# zx81c.net
KiCad netlist of a schematic drawn in EAGLE
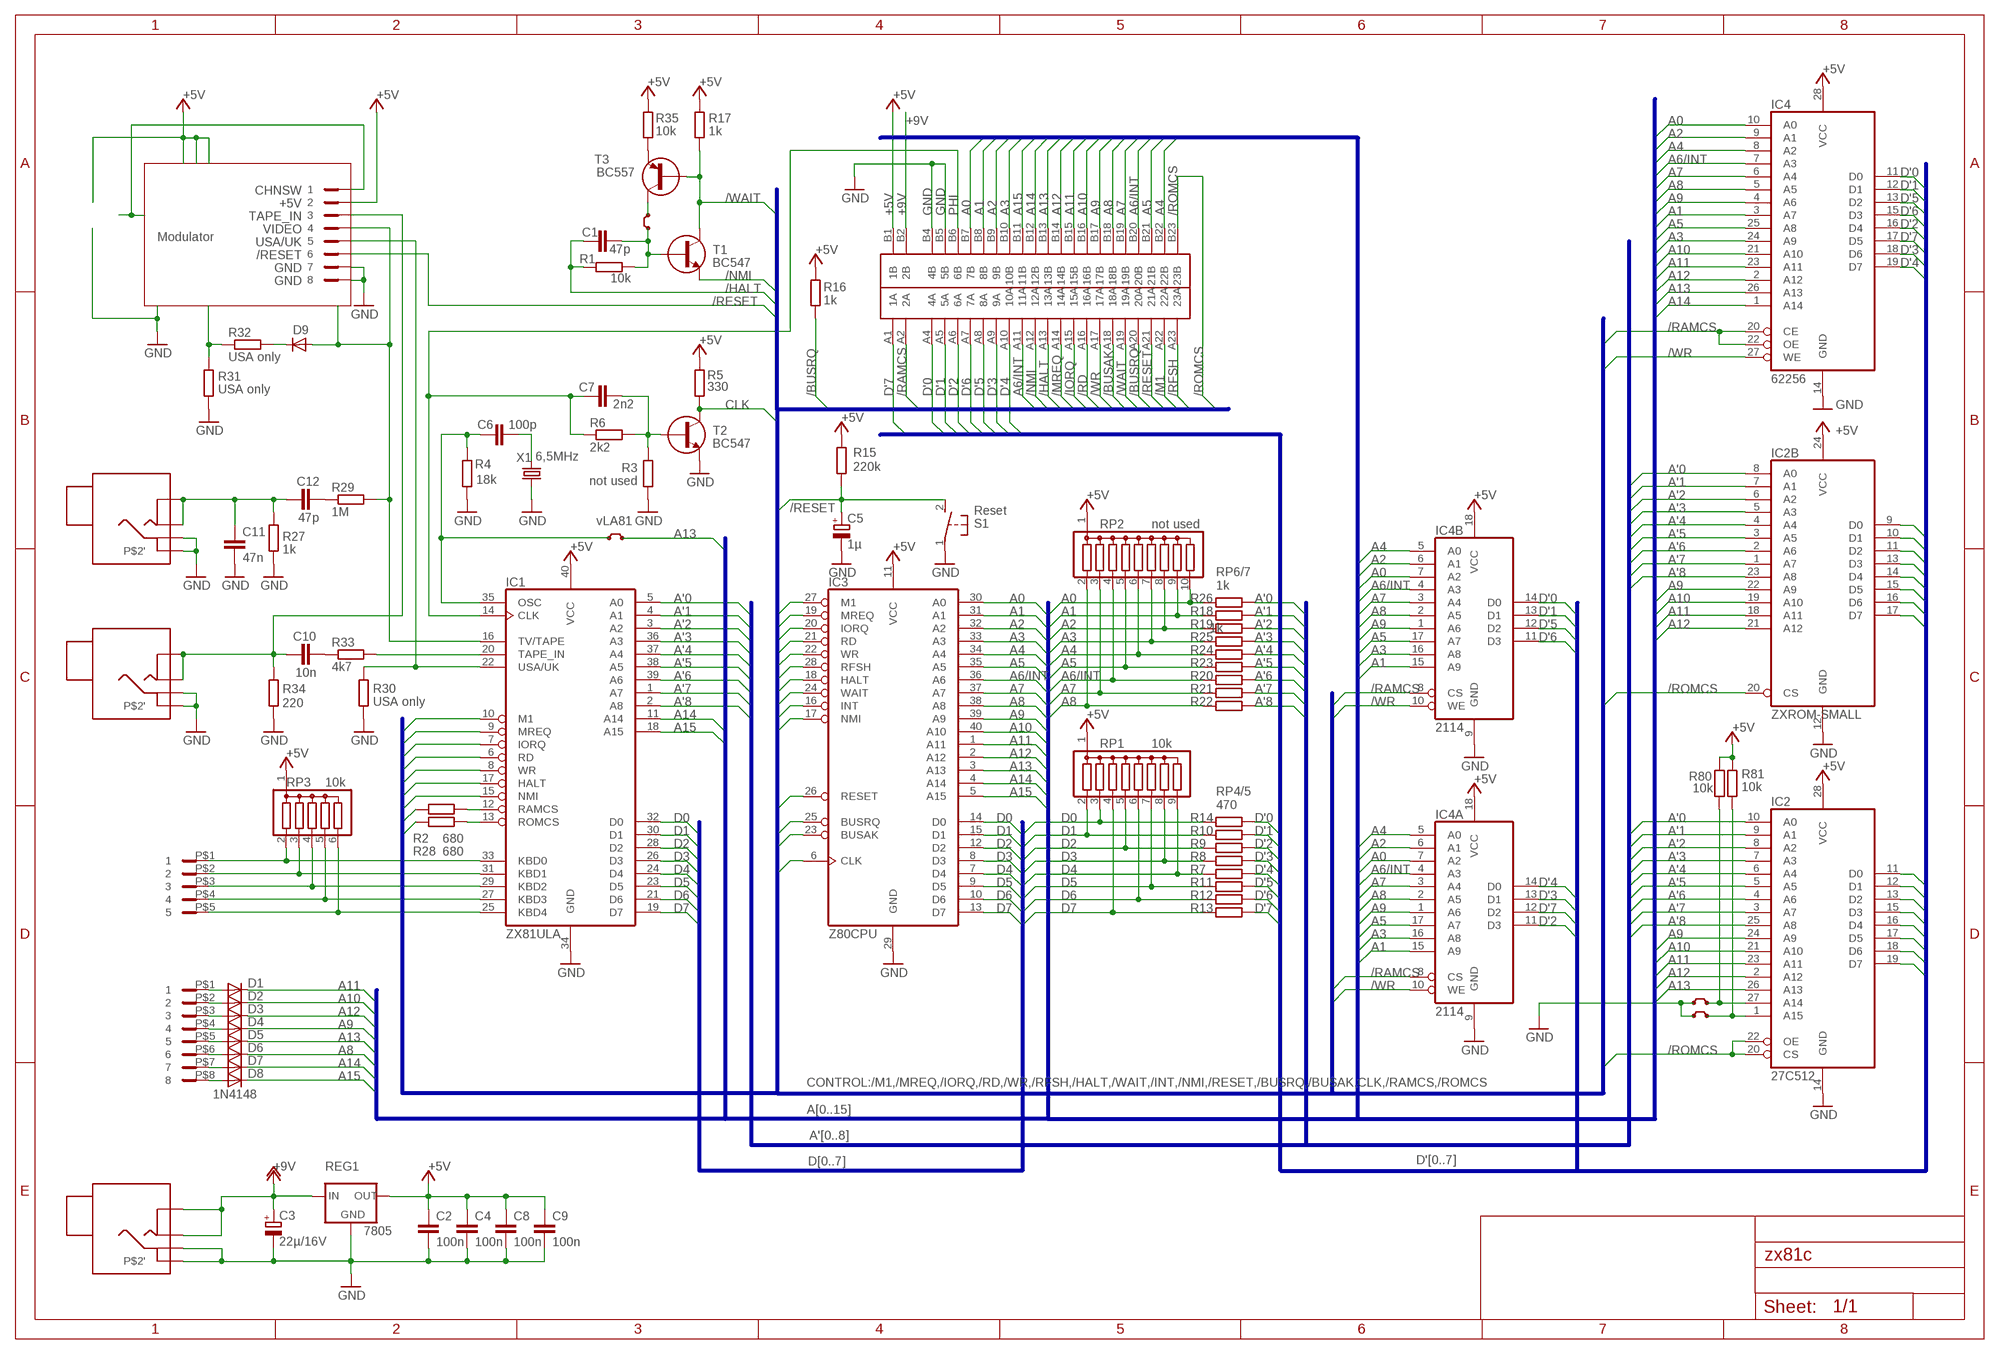
[diagram p0: schematic, sheet 1]

(export (version "E")
  (design (tool "Eeschema 10.0.6"))
  (components
    (comp (ref "C1")
      (value "47p")
      (footprint "eagle-import:C025-025X050")
      (libsource (lib "eagle-import") (part "C"))
    )
    (comp (ref "C2")
      (value "100n")
      (footprint "eagle-import:C025-025X050")
      (libsource (lib "eagle-import") (part "C"))
    )
    (comp (ref "C3")
      (value "22µ/16V")
      (footprint "eagle-import:E5-5")
      (libsource (lib "eagle-import") (part "CPOLE5-5"))
    )
    (comp (ref "C4")
      (value "100n")
      (footprint "eagle-import:C025-025X050")
      (libsource (lib "eagle-import") (part "C"))
    )
    (comp (ref "C5")
      (value "1µ")
      (footprint "eagle-import:E3,8-5")
      (libsource (lib "eagle-import") (part "CPOLE3,8-5"))
    )
    (comp (ref "C6")
      (value "100p")
      (footprint "eagle-import:C025-025X050")
      (libsource (lib "eagle-import") (part "C"))
    )
    (comp (ref "C7")
      (value "2n2")
      (footprint "eagle-import:C025-025X050")
      (libsource (lib "eagle-import") (part "C"))
    )
    (comp (ref "C8")
      (value "100n")
      (footprint "eagle-import:C025-025X050")
      (libsource (lib "eagle-import") (part "C"))
    )
    (comp (ref "C9")
      (value "100n")
      (footprint "eagle-import:C025-025X050")
      (libsource (lib "eagle-import") (part "C"))
    )
    (comp (ref "C10")
      (value "10n")
      (footprint "eagle-import:C025-025X050")
      (libsource (lib "eagle-import") (part "C"))
    )
    (comp (ref "C11")
      (value "47n")
      (footprint "eagle-import:C025-025X050")
      (libsource (lib "eagle-import") (part "C"))
    )
    (comp (ref "C12")
      (value "47p")
      (footprint "eagle-import:C025-025X050")
      (libsource (lib "eagle-import") (part "C"))
    )
    (comp (ref "D1")
      (value "1N4148")
      (footprint "eagle-import:D-TR-10")
      (libsource (lib "eagle-import") (part "DIODEDTR"))
    )
    (comp (ref "D2")
      (value "1N4148")
      (footprint "eagle-import:D-TR-10")
      (libsource (lib "eagle-import") (part "DIODEDTR"))
    )
    (comp (ref "D3")
      (value "1N4148")
      (footprint "eagle-import:D-TR-10")
      (libsource (lib "eagle-import") (part "DIODEDTR"))
    )
    (comp (ref "D4")
      (value "1N4148")
      (footprint "eagle-import:D-TR-10")
      (libsource (lib "eagle-import") (part "DIODEDTR"))
    )
    (comp (ref "D5")
      (value "1N4148")
      (footprint "eagle-import:D-TR-10")
      (libsource (lib "eagle-import") (part "DIODEDTR"))
    )
    (comp (ref "D6")
      (value "1N4148")
      (footprint "eagle-import:D-TR-10")
      (libsource (lib "eagle-import") (part "DIODEDTR"))
    )
    (comp (ref "D7")
      (value "1N4148")
      (footprint "eagle-import:D-TR-10")
      (libsource (lib "eagle-import") (part "DIODEDTR"))
    )
    (comp (ref "D8")
      (value "1N4148")
      (footprint "eagle-import:D-TR-10")
      (libsource (lib "eagle-import") (part "DIODEDTR"))
    )
    (comp (ref "D9")
      (value "DIODED15")
      (footprint "eagle-import:D15")
      (libsource (lib "eagle-import") (part "DIODED15"))
    )
    (comp (ref "IC1")
      (value "ZX81ULA")
      (footprint "eagle-import:DIL40")
      (libsource (lib "eagle-import") (part "ZX81ULA"))
    )
    (comp (ref "IC2")
      (value "27C512")
      (footprint "eagle-import:DIL28")
      (libsource (lib "eagle-import") (part "27C512"))
    )
    (comp (ref "IC2B")
      (value "ZXROM-SMALL")
      (footprint "eagle-import:DIL24")
      (libsource (lib "eagle-import") (part "ZXROM-SMALL"))
    )
    (comp (ref "IC3")
      (value "Z80CPU")
      (footprint "eagle-import:DIL40")
      (libsource (lib "eagle-import") (part "Z80CPU"))
    )
    (comp (ref "IC4")
      (value "62256")
      (footprint "eagle-import:DIL28")
      (libsource (lib "eagle-import") (part "62256"))
    )
    (comp (ref "IC4A")
      (value "2114")
      (footprint "eagle-import:DIL18")
      (libsource (lib "eagle-import") (part "2114"))
    )
    (comp (ref "IC4B")
      (value "2114")
      (footprint "eagle-import:DIL18")
      (libsource (lib "eagle-import") (part "2114"))
    )
    (comp (ref "JP1")
      (value "JUMPER")
      (footprint "eagle-import:JUMPER")
      (libsource (lib "eagle-import") (part "JUMPER"))
    )
    (comp (ref "JP2")
      (value "JUMPER")
      (footprint "eagle-import:JUMPER")
      (libsource (lib "eagle-import") (part "JUMPER"))
    )
    (comp (ref "JP3")
      (value "JUMPER")
      (footprint "eagle-import:JUMPER")
      (libsource (lib "eagle-import") (part "JUMPER"))
    )
    (comp (ref "JP4")
      (value "JUMPER")
      (footprint "eagle-import:JUMPER")
      (libsource (lib "eagle-import") (part "JUMPER"))
    )
    (comp (ref "K1")
      (value "ZX81CONN")
      (footprint "eagle-import:ZX81CON")
      (libsource (lib "eagle-import") (part "ZX81CONN"))
    )
    (comp (ref "K2")
      (value "MIC")
      (footprint "eagle-import:ZXKLINKE4POL")
      (libsource (lib "eagle-import") (part "ZXKLINKE4POL"))
    )
    (comp (ref "K3")
      (value "EAR")
      (footprint "eagle-import:ZXKLINKE4POL")
      (libsource (lib "eagle-import") (part "ZXKLINKE4POL"))
    )
    (comp (ref "K4")
      (value "DCIN")
      (footprint "eagle-import:ZXKLINKE4POL")
      (libsource (lib "eagle-import") (part "ZXKLINKE4POL"))
    )
    (comp (ref "K5")
      (value "PINHEAD-2X4")
      (footprint "eagle-import:PINHEAD2X4")
      (libsource (lib "eagle-import") (part "PINHEAD-2X4"))
    )
    (comp (ref "KB1")
      (value "ZXKBD5CON")
      (footprint "eagle-import:ZXKDB5")
      (libsource (lib "eagle-import") (part "ZXKBD5CON"))
    )
    (comp (ref "KB2")
      (value "ZXKBD8CON")
      (footprint "eagle-import:ZXKBD8")
      (libsource (lib "eagle-import") (part "ZXKBD8CON"))
    )
    (comp (ref "R1")
      (value "10k")
      (footprint "eagle-import:R207_12")
      (libsource (lib "eagle-import") (part "RR207/12"))
    )
    (comp (ref "R2")
      (value "680")
      (footprint "eagle-import:R207_12")
      (libsource (lib "eagle-import") (part "RR207/12"))
    )
    (comp (ref "R3")
      (value "not used")
      (footprint "eagle-import:R207_12")
      (libsource (lib "eagle-import") (part "RR207/12"))
    )
    (comp (ref "R4")
      (value "18k")
      (footprint "eagle-import:R207_12")
      (libsource (lib "eagle-import") (part "RR207/12"))
    )
    (comp (ref "R5")
      (value "330")
      (footprint "eagle-import:R207_12")
      (libsource (lib "eagle-import") (part "RR207/12"))
    )
    (comp (ref "R6")
      (value "2k2")
      (footprint "eagle-import:R207_12")
      (libsource (lib "eagle-import") (part "RR207/12"))
    )
    (comp (ref "R15")
      (value "220k")
      (footprint "eagle-import:R207_12")
      (libsource (lib "eagle-import") (part "RR207/12"))
    )
    (comp (ref "R16")
      (value "1k")
      (footprint "eagle-import:R207_12")
      (libsource (lib "eagle-import") (part "RR207/12"))
    )
    (comp (ref "R17")
      (value "1k")
      (footprint "eagle-import:R207_12")
      (libsource (lib "eagle-import") (part "RR207/12"))
    )
    (comp (ref "R27")
      (value "1k")
      (footprint "eagle-import:R207_12")
      (libsource (lib "eagle-import") (part "RR207/12"))
    )
    (comp (ref "R28")
      (value "680")
      (footprint "eagle-import:R207_12")
      (libsource (lib "eagle-import") (part "RR207/12"))
    )
    (comp (ref "R29")
      (value "1M")
      (footprint "eagle-import:R207_12")
      (libsource (lib "eagle-import") (part "RR207/12"))
    )
    (comp (ref "R30")
      (value "USA only")
      (footprint "eagle-import:R207_12")
      (libsource (lib "eagle-import") (part "RR207/12"))
    )
    (comp (ref "R31")
      (value "USA only")
      (footprint "eagle-import:R207_12")
      (libsource (lib "eagle-import") (part "RR207/12"))
    )
    (comp (ref "R32")
      (value "USA only")
      (footprint "eagle-import:R207_12")
      (libsource (lib "eagle-import") (part "RR207/12"))
    )
    (comp (ref "R33")
      (value "4k7")
      (footprint "eagle-import:R207_12")
      (libsource (lib "eagle-import") (part "RR207/12"))
    )
    (comp (ref "R34")
      (value "220")
      (footprint "eagle-import:R207_12")
      (libsource (lib "eagle-import") (part "RR207/12"))
    )
    (comp (ref "R35")
      (value "10k")
      (footprint "eagle-import:R207_12")
      (libsource (lib "eagle-import") (part "RR207/12"))
    )
    (comp (ref "R80")
      (value "10k")
      (footprint "eagle-import:R207_12")
      (libsource (lib "eagle-import") (part "RR207/12"))
    )
    (comp (ref "R81")
      (value "10k")
      (footprint "eagle-import:R207_12")
      (libsource (lib "eagle-import") (part "RR207/12"))
    )
    (comp (ref "REG1")
      (value "7805")
      (footprint "eagle-import:78XXL")
      (libsource (lib "eagle-import") (part "78XX"))
    )
    (comp (ref "RP1")
      (value "10k")
      (footprint "eagle-import:SIL9")
      (libsource (lib "eagle-import") (part "RSIL8"))
    )
    (comp (ref "RP2")
      (value "not used")
      (footprint "eagle-import:SIL10")
      (libsource (lib "eagle-import") (part "RSIL9"))
    )
    (comp (ref "RP3")
      (value "10k")
      (footprint "eagle-import:SIL6")
      (libsource (lib "eagle-import") (part "RSIL5"))
    )
    (comp (ref "RP4")
      (value "470")
      (footprint "eagle-import:SIL8P")
      (libsource (lib "eagle-import") (part "RSILP4"))
    )
    (comp (ref "RP5")
      (value "470")
      (footprint "eagle-import:SIL8P")
      (libsource (lib "eagle-import") (part "RSILP4"))
    )
    (comp (ref "RP6")
      (value "1k")
      (footprint "eagle-import:SIL8P")
      (libsource (lib "eagle-import") (part "RSILP4"))
    )
    (comp (ref "RP7")
      (value "1k")
      (footprint "eagle-import:SIL10P")
      (libsource (lib "eagle-import") (part "RSILP5"))
    )
    (comp (ref "S1")
      (value "Reset")
      (footprint "eagle-import:B3F-31XX")
      (fields (field (name "MPN") "B3F-3100"))
      (libsource (lib "eagle-import") (part "31-XX"))
    )
    (comp (ref "T1")
      (value "BC547")
      (footprint "eagle-import:TO92")
      (libsource (lib "eagle-import") (part "T-NPN-BC547"))
    )
    (comp (ref "T2")
      (value "BC547")
      (footprint "eagle-import:TO92")
      (libsource (lib "eagle-import") (part "T-NPN-BC547"))
    )
    (comp (ref "T3")
      (value "BC557")
      (footprint "eagle-import:TO92")
      (libsource (lib "eagle-import") (part "T-PNP-BC557"))
    )
    (comp (ref "X1")
      (value "6,5MHz")
      (footprint "eagle-import:HC49")
      (libsource (lib "eagle-import") (part "CRYSTAL"))
    )
  )
  (nets
    (net (code "4") (name "+5V") (class "Default")
      (node (ref "C2") (pin "1") (pinfunction "1_1") (pintype "passive"))
      (node (ref "C4") (pin "1") (pinfunction "1_1") (pintype "passive"))
      (node (ref "C8") (pin "1") (pinfunction "1_1") (pintype "passive"))
      (node (ref "C9") (pin "1") (pinfunction "1_1") (pintype "passive"))
      (node (ref "IC1") (pin "40") (pinfunction "VCC_40") (pintype "power_in"))
      (node (ref "IC2") (pin "28") (pinfunction "VCC_28") (pintype "power_in"))
      (node (ref "IC2B") (pin "24") (pinfunction "VCC_24") (pintype "power_in"))
      (node (ref "IC3") (pin "11") (pinfunction "VCC_11") (pintype "power_in"))
      (node (ref "IC4") (pin "28") (pinfunction "VCC_28") (pintype "power_in"))
      (node (ref "IC4A") (pin "18") (pinfunction "VCC_18") (pintype "power_in"))
      (node (ref "IC4B") (pin "18") (pinfunction "VCC_18") (pintype "power_in"))
      (node (ref "K1") (pin "B1") (pinfunction "1B_B1") (pintype "bidirectional"))
      (node (ref "K5") (pin "2") (pinfunction "2_2") (pintype "bidirectional"))
      (node (ref "R15") (pin "2") (pinfunction "2_2") (pintype "passive"))
      (node (ref "R16") (pin "1") (pinfunction "1_1") (pintype "passive"))
      (node (ref "R17") (pin "2") (pinfunction "2_2") (pintype "passive"))
      (node (ref "R35") (pin "2") (pinfunction "2_2") (pintype "passive"))
      (node (ref "R5") (pin "2") (pinfunction "2_2") (pintype "passive"))
      (node (ref "R80") (pin "2") (pinfunction "2_2") (pintype "passive"))
      (node (ref "R81") (pin "2") (pinfunction "2_2") (pintype "passive"))
      (node (ref "REG1") (pin "OUT") (pinfunction "OUT_OUT") (pintype "passive"))
      (node (ref "RP1") (pin "1") (pinfunction "1_1") (pintype "passive"))
      (node (ref "RP2") (pin "1") (pinfunction "1_1") (pintype "passive"))
      (node (ref "RP3") (pin "1") (pinfunction "1_1") (pintype "passive"))
    )
    (net (code "5") (name "+9V") (class "Default")
      (node (ref "C3") (pin "+") (pinfunction "+_+") (pintype "passive"))
      (node (ref "K1") (pin "B2") (pinfunction "2B_B2") (pintype "bidirectional"))
      (node (ref "K4") (pin "1") (pinfunction "P$1_1") (pintype "bidirectional"))
      (node (ref "K4") (pin "1'") (pinfunction "P$1'_1'") (pintype "bidirectional"))
      (node (ref "REG1") (pin "IN") (pinfunction "IN_IN") (pintype "input"))
    )
    (net (code "6") (name "/A'0") (class "Default")
      (node (ref "IC1") (pin "5") (pinfunction "A0_5") (pintype "output"))
      (node (ref "IC2") (pin "10") (pinfunction "A0_10") (pintype "input"))
      (node (ref "IC2B") (pin "8") (pinfunction "A0_8") (pintype "input"))
      (node (ref "RP6") (pin "7") (pinfunction "1_7") (pintype "passive"))
    )
    (net (code "7") (name "/A'1") (class "Default")
      (node (ref "IC1") (pin "4") (pinfunction "A1_4") (pintype "output"))
      (node (ref "IC2") (pin "9") (pinfunction "A1_9") (pintype "input"))
      (node (ref "IC2B") (pin "7") (pinfunction "A1_7") (pintype "input"))
      (node (ref "RP7") (pin "2") (pinfunction "2_2") (pintype "passive"))
    )
    (net (code "8") (name "/A'2") (class "Default")
      (node (ref "IC1") (pin "3") (pinfunction "A2_3") (pintype "output"))
      (node (ref "IC2") (pin "8") (pinfunction "A2_8") (pintype "input"))
      (node (ref "IC2B") (pin "6") (pinfunction "A2_6") (pintype "input"))
      (node (ref "RP7") (pin "3") (pinfunction "1_3") (pintype "passive"))
    )
    (net (code "9") (name "/A'3") (class "Default")
      (node (ref "IC1") (pin "36") (pinfunction "A3_36") (pintype "output"))
      (node (ref "IC2") (pin "7") (pinfunction "A3_7") (pintype "input"))
      (node (ref "IC2B") (pin "5") (pinfunction "A3_5") (pintype "input"))
      (node (ref "RP6") (pin "5") (pinfunction "1_5") (pintype "passive"))
    )
    (net (code "10") (name "/A'4") (class "Default")
      (node (ref "IC1") (pin "37") (pinfunction "A4_37") (pintype "output"))
      (node (ref "IC2") (pin "6") (pinfunction "A4_6") (pintype "input"))
      (node (ref "IC2B") (pin "4") (pinfunction "A4_4") (pintype "input"))
      (node (ref "RP6") (pin "3") (pinfunction "1_3") (pintype "passive"))
    )
    (net (code "11") (name "/A'5") (class "Default")
      (node (ref "IC1") (pin "38") (pinfunction "A5_38") (pintype "output"))
      (node (ref "IC2") (pin "5") (pinfunction "A5_5") (pintype "input"))
      (node (ref "IC2B") (pin "3") (pinfunction "A5_3") (pintype "input"))
      (node (ref "RP6") (pin "1") (pinfunction "1_1") (pintype "passive"))
    )
    (net (code "12") (name "/A'6") (class "Default")
      (node (ref "IC1") (pin "39") (pinfunction "A6_39") (pintype "output"))
      (node (ref "IC2") (pin "4") (pinfunction "A6_4") (pintype "input"))
      (node (ref "IC2B") (pin "2") (pinfunction "A6_2") (pintype "input"))
      (node (ref "RP7") (pin "5") (pinfunction "1_5") (pintype "passive"))
    )
    (net (code "13") (name "/A'7") (class "Default")
      (node (ref "IC1") (pin "1") (pinfunction "A7_1") (pintype "output"))
      (node (ref "IC2") (pin "3") (pinfunction "A7_3") (pintype "input"))
      (node (ref "IC2B") (pin "1") (pinfunction "A7_1") (pintype "input"))
      (node (ref "RP7") (pin "7") (pinfunction "1_7") (pintype "passive"))
    )
    (net (code "14") (name "/A'8") (class "Default")
      (node (ref "IC1") (pin "2") (pinfunction "A8_2") (pintype "output"))
      (node (ref "IC2") (pin "25") (pinfunction "A8_25") (pintype "input"))
      (node (ref "IC2B") (pin "23") (pinfunction "A8_23") (pintype "input"))
      (node (ref "RP7") (pin "9") (pinfunction "1_9") (pintype "passive"))
    )
    (net (code "16") (name "/A0") (class "Default")
      (node (ref "IC3") (pin "30") (pinfunction "A0_30") (pintype "output"))
      (node (ref "IC4") (pin "10") (pinfunction "A0_10") (pintype "input"))
      (node (ref "IC4A") (pin "7") (pinfunction "A2_7") (pintype "output"))
      (node (ref "IC4B") (pin "7") (pinfunction "A2_7") (pintype "output"))
      (node (ref "K1") (pin "B7") (pinfunction "7B_B7") (pintype "bidirectional"))
      (node (ref "RP2") (pin "10") (pinfunction "10_10") (pintype "passive"))
      (node (ref "RP6") (pin "8") (pinfunction "2_8") (pintype "passive"))
    )
    (net (code "17") (name "/A1") (class "Default")
      (node (ref "IC3") (pin "31") (pinfunction "A1_31") (pintype "output"))
      (node (ref "IC4") (pin "3") (pinfunction "A7_3") (pintype "input"))
      (node (ref "IC4A") (pin "15") (pinfunction "A9_15") (pintype "output"))
      (node (ref "IC4B") (pin "15") (pinfunction "A9_15") (pintype "output"))
      (node (ref "K1") (pin "B8") (pinfunction "8B_B8") (pintype "bidirectional"))
      (node (ref "RP2") (pin "9") (pinfunction "9_9") (pintype "passive"))
      (node (ref "RP7") (pin "1") (pinfunction "1_1") (pintype "passive"))
    )
    (net (code "18") (name "/A2") (class "Default")
      (node (ref "IC3") (pin "32") (pinfunction "A2_32") (pintype "output"))
      (node (ref "IC4") (pin "9") (pinfunction "A1_9") (pintype "input"))
      (node (ref "IC4A") (pin "6") (pinfunction "A1_6") (pintype "output"))
      (node (ref "IC4B") (pin "6") (pinfunction "A1_6") (pintype "output"))
      (node (ref "K1") (pin "B9") (pinfunction "9B_B9") (pintype "bidirectional"))
      (node (ref "RP2") (pin "8") (pinfunction "8_8") (pintype "passive"))
      (node (ref "RP7") (pin "4") (pinfunction "2_4") (pintype "passive"))
    )
    (net (code "19") (name "/A3") (class "Default")
      (node (ref "IC3") (pin "33") (pinfunction "A3_33") (pintype "output"))
      (node (ref "IC4") (pin "24") (pinfunction "A9_24") (pintype "input"))
      (node (ref "IC4A") (pin "16") (pinfunction "A8_16") (pintype "output"))
      (node (ref "IC4B") (pin "16") (pinfunction "A8_16") (pintype "output"))
      (node (ref "K1") (pin "B10") (pinfunction "10B_B10") (pintype "bidirectional"))
      (node (ref "RP2") (pin "7") (pinfunction "7_7") (pintype "passive"))
      (node (ref "RP6") (pin "6") (pinfunction "2_6") (pintype "passive"))
    )
    (net (code "20") (name "/A4") (class "Default")
      (node (ref "IC3") (pin "34") (pinfunction "A4_34") (pintype "output"))
      (node (ref "IC4") (pin "8") (pinfunction "A2_8") (pintype "input"))
      (node (ref "IC4A") (pin "5") (pinfunction "A0_5") (pintype "output"))
      (node (ref "IC4B") (pin "5") (pinfunction "A0_5") (pintype "output"))
      (node (ref "K1") (pin "B22") (pinfunction "22B_B22") (pintype "bidirectional"))
      (node (ref "RP2") (pin "6") (pinfunction "6_6") (pintype "passive"))
      (node (ref "RP6") (pin "4") (pinfunction "2_4") (pintype "passive"))
    )
    (net (code "21") (name "/A5") (class "Default")
      (node (ref "IC3") (pin "35") (pinfunction "A5_35") (pintype "output"))
      (node (ref "IC4") (pin "25") (pinfunction "A8_25") (pintype "input"))
      (node (ref "IC4A") (pin "17") (pinfunction "A7_17") (pintype "output"))
      (node (ref "IC4B") (pin "17") (pinfunction "A7_17") (pintype "output"))
      (node (ref "K1") (pin "B21") (pinfunction "21B_B21") (pintype "bidirectional"))
      (node (ref "RP2") (pin "5") (pinfunction "5_5") (pintype "passive"))
      (node (ref "RP6") (pin "2") (pinfunction "2_2") (pintype "passive"))
    )
    (net (code "22") (name "/A6{slash}INT") (class "Default")
      (node (ref "IC3") (pin "16") (pinfunction "INT_16") (pintype "input"))
      (node (ref "IC3") (pin "36") (pinfunction "A6_36") (pintype "output"))
      (node (ref "IC4") (pin "7") (pinfunction "A3_7") (pintype "input"))
      (node (ref "IC4A") (pin "4") (pinfunction "A3_4") (pintype "output"))
      (node (ref "IC4B") (pin "4") (pinfunction "A3_4") (pintype "output"))
      (node (ref "K1") (pin "A11") (pinfunction "11A_A11") (pintype "bidirectional"))
      (node (ref "K1") (pin "B20") (pinfunction "20B_B20") (pintype "bidirectional"))
      (node (ref "RP2") (pin "4") (pinfunction "4_4") (pintype "passive"))
      (node (ref "RP7") (pin "6") (pinfunction "2_6") (pintype "passive"))
    )
    (net (code "23") (name "/A7") (class "Default")
      (node (ref "IC3") (pin "37") (pinfunction "A7_37") (pintype "output"))
      (node (ref "IC4") (pin "6") (pinfunction "A4_6") (pintype "input"))
      (node (ref "IC4A") (pin "3") (pinfunction "A4_3") (pintype "output"))
      (node (ref "IC4B") (pin "3") (pinfunction "A4_3") (pintype "output"))
      (node (ref "K1") (pin "B19") (pinfunction "19B_B19") (pintype "bidirectional"))
      (node (ref "RP2") (pin "3") (pinfunction "3_3") (pintype "passive"))
      (node (ref "RP7") (pin "8") (pinfunction "2_8") (pintype "passive"))
    )
    (net (code "24") (name "/A8") (class "Default")
      (node (ref "D6") (pin "C") (pinfunction "C_C") (pintype "passive"))
      (node (ref "IC3") (pin "38") (pinfunction "A8_38") (pintype "output"))
      (node (ref "IC4") (pin "5") (pinfunction "A5_5") (pintype "input"))
      (node (ref "IC4A") (pin "2") (pinfunction "A5_2") (pintype "output"))
      (node (ref "IC4B") (pin "2") (pinfunction "A5_2") (pintype "output"))
      (node (ref "K1") (pin "B18") (pinfunction "18B_B18") (pintype "bidirectional"))
      (node (ref "RP2") (pin "2") (pinfunction "2_2") (pintype "passive"))
      (node (ref "RP7") (pin "10") (pinfunction "2_10") (pintype "passive"))
    )
    (net (code "25") (name "/A9") (class "Default")
      (node (ref "D4") (pin "C") (pinfunction "C_C") (pintype "passive"))
      (node (ref "IC2") (pin "24") (pinfunction "A9_24") (pintype "input"))
      (node (ref "IC2B") (pin "22") (pinfunction "A9_22") (pintype "input"))
      (node (ref "IC3") (pin "39") (pinfunction "A9_39") (pintype "output"))
      (node (ref "IC4") (pin "4") (pinfunction "A6_4") (pintype "input"))
      (node (ref "IC4A") (pin "1") (pinfunction "A6_1") (pintype "output"))
      (node (ref "IC4B") (pin "1") (pinfunction "A6_1") (pintype "output"))
      (node (ref "K1") (pin "B17") (pinfunction "17B_B17") (pintype "bidirectional"))
    )
    (net (code "26") (name "/A10") (class "Default")
      (node (ref "D2") (pin "C") (pinfunction "C_C") (pintype "passive"))
      (node (ref "IC2") (pin "21") (pinfunction "A10_21") (pintype "input"))
      (node (ref "IC2B") (pin "19") (pinfunction "A10_19") (pintype "input"))
      (node (ref "IC3") (pin "40") (pinfunction "A10_40") (pintype "output"))
      (node (ref "IC4") (pin "21") (pinfunction "A10_21") (pintype "input"))
      (node (ref "K1") (pin "B16") (pinfunction "16B_B16") (pintype "bidirectional"))
    )
    (net (code "27") (name "/A11") (class "Default")
      (node (ref "D1") (pin "C") (pinfunction "C_C") (pintype "passive"))
      (node (ref "IC2") (pin "23") (pinfunction "A11_23") (pintype "input"))
      (node (ref "IC2B") (pin "18") (pinfunction "A11_18") (pintype "input"))
      (node (ref "IC3") (pin "1") (pinfunction "A11_1") (pintype "output"))
      (node (ref "IC4") (pin "23") (pinfunction "A11_23") (pintype "input"))
      (node (ref "K1") (pin "B15") (pinfunction "15B_B15") (pintype "bidirectional"))
    )
    (net (code "28") (name "/A12") (class "Default")
      (node (ref "D3") (pin "C") (pinfunction "C_C") (pintype "passive"))
      (node (ref "IC2") (pin "2") (pinfunction "A12_2") (pintype "input"))
      (node (ref "IC2B") (pin "21") (pinfunction "A12_21") (pintype "input"))
      (node (ref "IC3") (pin "2") (pinfunction "A12_2") (pintype "output"))
      (node (ref "IC4") (pin "2") (pinfunction "A12_2") (pintype "input"))
      (node (ref "K1") (pin "B14") (pinfunction "14B_B14") (pintype "bidirectional"))
    )
    (net (code "29") (name "/A13") (class "Default")
      (node (ref "D5") (pin "C") (pinfunction "C_C") (pintype "passive"))
      (node (ref "IC2") (pin "26") (pinfunction "A13_26") (pintype "input"))
      (node (ref "IC3") (pin "3") (pinfunction "A13_3") (pintype "output"))
      (node (ref "IC4") (pin "26") (pinfunction "A13_26") (pintype "input"))
      (node (ref "JP3") (pin "2") (pinfunction "P$2_2") (pintype "bidirectional"))
      (node (ref "K1") (pin "B13") (pinfunction "13B_B13") (pintype "bidirectional"))
    )
    (net (code "30") (name "/A14") (class "Default")
      (node (ref "D7") (pin "C") (pinfunction "C_C") (pintype "passive"))
      (node (ref "IC1") (pin "11") (pinfunction "A14_11") (pintype "output"))
      (node (ref "IC3") (pin "4") (pinfunction "A14_4") (pintype "output"))
      (node (ref "IC4") (pin "1") (pinfunction "A14_1") (pintype "input"))
      (node (ref "K1") (pin "B12") (pinfunction "12B_B12") (pintype "bidirectional"))
    )
    (net (code "31") (name "/A15") (class "Default")
      (node (ref "D8") (pin "C") (pinfunction "C_C") (pintype "passive"))
      (node (ref "IC1") (pin "18") (pinfunction "A15_18") (pintype "output"))
      (node (ref "IC3") (pin "5") (pinfunction "A15_5") (pintype "output"))
      (node (ref "K1") (pin "B11") (pinfunction "11B_B11") (pintype "bidirectional"))
    )
    (net (code "33") (name "/CHNSW") (class "Default")
      (node (ref "K5") (pin "1") (pinfunction "1_1") (pintype "bidirectional"))
    )
    (net (code "34") (name "/CLK") (class "Default")
      (node (ref "IC3") (pin "6") (pinfunction "CLK_6") (pintype "input"))
      (node (ref "R5") (pin "1") (pinfunction "1_1") (pintype "passive"))
      (node (ref "T2") (pin "C") (pinfunction "C_C") (pintype "passive"))
    )
    (net (code "35") (name "/D'0") (class "Default")
      (node (ref "IC2") (pin "11") (pinfunction "D0_11") (pintype "bidirectional"))
      (node (ref "IC2B") (pin "9") (pinfunction "D0_9") (pintype "output"))
      (node (ref "IC4") (pin "11") (pinfunction "D0_11") (pintype "bidirectional"))
      (node (ref "IC4B") (pin "14") (pinfunction "D0_14") (pintype "bidirectional"))
      (node (ref "K1") (pin "A4") (pinfunction "4A_A4") (pintype "bidirectional"))
      (node (ref "RP5") (pin "8") (pinfunction "2_8") (pintype "passive"))
    )
    (net (code "36") (name "/D'1") (class "Default")
      (node (ref "IC2") (pin "12") (pinfunction "D1_12") (pintype "bidirectional"))
      (node (ref "IC2B") (pin "10") (pinfunction "D1_10") (pintype "output"))
      (node (ref "IC4") (pin "12") (pinfunction "D1_12") (pintype "bidirectional"))
      (node (ref "IC4B") (pin "13") (pinfunction "D1_13") (pintype "bidirectional"))
      (node (ref "K1") (pin "A5") (pinfunction "5A_A5") (pintype "bidirectional"))
      (node (ref "RP4") (pin "8") (pinfunction "2_8") (pintype "passive"))
    )
    (net (code "37") (name "/D'2") (class "Default")
      (node (ref "IC2") (pin "13") (pinfunction "D2_13") (pintype "bidirectional"))
      (node (ref "IC2B") (pin "11") (pinfunction "D2_11") (pintype "output"))
      (node (ref "IC4") (pin "16") (pinfunction "D4_16") (pintype "bidirectional"))
      (node (ref "IC4A") (pin "11") (pinfunction "D3_11") (pintype "bidirectional"))
      (node (ref "K1") (pin "A6") (pinfunction "6A_A6") (pintype "bidirectional"))
      (node (ref "RP4") (pin "6") (pinfunction "2_6") (pintype "passive"))
    )
    (net (code "38") (name "/D'3") (class "Default")
      (node (ref "IC2") (pin "15") (pinfunction "D3_15") (pintype "bidirectional"))
      (node (ref "IC2B") (pin "13") (pinfunction "D3_13") (pintype "output"))
      (node (ref "IC4") (pin "18") (pinfunction "D6_18") (pintype "bidirectional"))
      (node (ref "IC4A") (pin "13") (pinfunction "D1_13") (pintype "bidirectional"))
      (node (ref "K1") (pin "A9") (pinfunction "9A_A9") (pintype "bidirectional"))
      (node (ref "RP4") (pin "4") (pinfunction "2_4") (pintype "passive"))
    )
    (net (code "39") (name "/D'4") (class "Default")
      (node (ref "IC2") (pin "16") (pinfunction "D4_16") (pintype "bidirectional"))
      (node (ref "IC2B") (pin "14") (pinfunction "D4_14") (pintype "output"))
      (node (ref "IC4") (pin "19") (pinfunction "D7_19") (pintype "bidirectional"))
      (node (ref "IC4A") (pin "14") (pinfunction "D0_14") (pintype "bidirectional"))
      (node (ref "K1") (pin "A10") (pinfunction "10A_A10") (pintype "bidirectional"))
      (node (ref "RP4") (pin "1") (pinfunction "1_1") (pintype "passive"))
    )
    (net (code "40") (name "/D'5") (class "Default")
      (node (ref "IC2") (pin "17") (pinfunction "D5_17") (pintype "bidirectional"))
      (node (ref "IC2B") (pin "15") (pinfunction "D5_15") (pintype "output"))
      (node (ref "IC4") (pin "13") (pinfunction "D2_13") (pintype "bidirectional"))
      (node (ref "IC4B") (pin "12") (pinfunction "D2_12") (pintype "bidirectional"))
      (node (ref "K1") (pin "A8") (pinfunction "8A_A8") (pintype "bidirectional"))
      (node (ref "RP5") (pin "1") (pinfunction "1_1") (pintype "passive"))
    )
    (net (code "41") (name "/D'6") (class "Default")
      (node (ref "IC2") (pin "18") (pinfunction "D6_18") (pintype "bidirectional"))
      (node (ref "IC2B") (pin "16") (pinfunction "D6_16") (pintype "output"))
      (node (ref "IC4") (pin "15") (pinfunction "D3_15") (pintype "bidirectional"))
      (node (ref "IC4B") (pin "11") (pinfunction "D3_11") (pintype "bidirectional"))
      (node (ref "K1") (pin "A7") (pinfunction "7A_A7") (pintype "bidirectional"))
      (node (ref "RP5") (pin "4") (pinfunction "2_4") (pintype "passive"))
    )
    (net (code "42") (name "/D'7") (class "Default")
      (node (ref "IC2") (pin "19") (pinfunction "D7_19") (pintype "bidirectional"))
      (node (ref "IC2B") (pin "17") (pinfunction "D7_17") (pintype "output"))
      (node (ref "IC4") (pin "17") (pinfunction "D5_17") (pintype "bidirectional"))
      (node (ref "IC4A") (pin "12") (pinfunction "D2_12") (pintype "bidirectional"))
      (node (ref "K1") (pin "A1") (pinfunction "1A_A1") (pintype "bidirectional"))
      (node (ref "RP5") (pin "5") (pinfunction "1_5") (pintype "passive"))
    )
    (net (code "44") (name "/D0") (class "Default")
      (node (ref "IC1") (pin "32") (pinfunction "D0_32") (pintype "bidirectional"))
      (node (ref "IC3") (pin "14") (pinfunction "D0_14") (pintype "bidirectional"))
      (node (ref "RP1") (pin "3") (pinfunction "3_3") (pintype "passive"))
      (node (ref "RP5") (pin "7") (pinfunction "1_7") (pintype "passive"))
    )
    (net (code "45") (name "/D1") (class "Default")
      (node (ref "IC1") (pin "30") (pinfunction "D1_30") (pintype "bidirectional"))
      (node (ref "IC3") (pin "15") (pinfunction "D1_15") (pintype "bidirectional"))
      (node (ref "RP1") (pin "2") (pinfunction "2_2") (pintype "passive"))
      (node (ref "RP4") (pin "7") (pinfunction "1_7") (pintype "passive"))
    )
    (net (code "46") (name "/D2") (class "Default")
      (node (ref "IC1") (pin "28") (pinfunction "D2_28") (pintype "bidirectional"))
      (node (ref "IC3") (pin "12") (pinfunction "D2_12") (pintype "bidirectional"))
      (node (ref "RP1") (pin "5") (pinfunction "5_5") (pintype "passive"))
      (node (ref "RP4") (pin "5") (pinfunction "1_5") (pintype "passive"))
    )
    (net (code "47") (name "/D3") (class "Default")
      (node (ref "IC1") (pin "26") (pinfunction "D3_26") (pintype "bidirectional"))
      (node (ref "IC3") (pin "8") (pinfunction "D3_8") (pintype "bidirectional"))
      (node (ref "RP1") (pin "8") (pinfunction "8_8") (pintype "passive"))
      (node (ref "RP4") (pin "3") (pinfunction "1_3") (pintype "passive"))
    )
    (net (code "48") (name "/D4") (class "Default")
      (node (ref "IC1") (pin "24") (pinfunction "D4_24") (pintype "bidirectional"))
      (node (ref "IC3") (pin "7") (pinfunction "D4_7") (pintype "bidirectional"))
      (node (ref "RP1") (pin "9") (pinfunction "9_9") (pintype "passive"))
      (node (ref "RP4") (pin "2") (pinfunction "2_2") (pintype "passive"))
    )
    (net (code "49") (name "/D5") (class "Default")
      (node (ref "IC1") (pin "23") (pinfunction "D5_23") (pintype "bidirectional"))
      (node (ref "IC3") (pin "9") (pinfunction "D5_9") (pintype "bidirectional"))
      (node (ref "RP1") (pin "7") (pinfunction "7_7") (pintype "passive"))
      (node (ref "RP5") (pin "2") (pinfunction "2_2") (pintype "passive"))
    )
    (net (code "50") (name "/D6") (class "Default")
      (node (ref "IC1") (pin "21") (pinfunction "D6_21") (pintype "bidirectional"))
      (node (ref "IC3") (pin "10") (pinfunction "D6_10") (pintype "bidirectional"))
      (node (ref "RP1") (pin "6") (pinfunction "6_6") (pintype "passive"))
      (node (ref "RP5") (pin "3") (pinfunction "1_3") (pintype "passive"))
    )
    (net (code "51") (name "/D7") (class "Default")
      (node (ref "IC1") (pin "19") (pinfunction "D7_19") (pintype "bidirectional"))
      (node (ref "IC3") (pin "13") (pinfunction "D7_13") (pintype "bidirectional"))
      (node (ref "RP1") (pin "4") (pinfunction "4_4") (pintype "passive"))
      (node (ref "RP5") (pin "6") (pinfunction "2_6") (pintype "passive"))
    )
    (net (code "53") (name "/PHI") (class "Default")
      (node (ref "C7") (pin "1") (pinfunction "1_1") (pintype "passive"))
      (node (ref "IC1") (pin "14") (pinfunction "CLK_14") (pintype "input"))
      (node (ref "K1") (pin "B6") (pinfunction "6B_B6") (pintype "bidirectional"))
      (node (ref "R6") (pin "1") (pinfunction "1_1") (pintype "passive"))
    )
    (net (code "54") (name "/TAPE_IN") (class "Default")
      (node (ref "C10") (pin "1") (pinfunction "1_1") (pintype "passive"))
      (node (ref "K3") (pin "1") (pinfunction "P$1_1") (pintype "bidirectional"))
      (node (ref "K3") (pin "1'") (pinfunction "P$1'_1'") (pintype "bidirectional"))
      (node (ref "K5") (pin "3") (pinfunction "3_3") (pintype "bidirectional"))
      (node (ref "R34") (pin "2") (pinfunction "2_2") (pintype "passive"))
    )
    (net (code "55") (name "/USA{slash}UK") (class "Default")
      (node (ref "IC1") (pin "22") (pinfunction "USA/UK_22") (pintype "output"))
      (node (ref "K5") (pin "5") (pinfunction "5_5") (pintype "bidirectional"))
      (node (ref "R30") (pin "1") (pinfunction "1_1") (pintype "passive"))
    )
    (net (code "56") (name "/VIDEO") (class "Default")
      (node (ref "D9") (pin "A") (pinfunction "A_A") (pintype "passive"))
      (node (ref "IC1") (pin "16") (pinfunction "TV/TAPE_16") (pintype "output"))
      (node (ref "K5") (pin "4") (pinfunction "4_4") (pintype "bidirectional"))
      (node (ref "R29") (pin "2") (pinfunction "2_2") (pintype "passive"))
    )
    (net (code "58") (name "/{slash}BUSAK") (class "Default")
      (node (ref "IC3") (pin "23") (pinfunction "BUSAK_23") (pintype "output"))
      (node (ref "K1") (pin "A18") (pinfunction "18A_A18") (pintype "bidirectional"))
    )
    (net (code "59") (name "/{slash}BUSRQ") (class "Default")
      (node (ref "IC3") (pin "25") (pinfunction "BUSRQ_25") (pintype "input"))
      (node (ref "K1") (pin "A20") (pinfunction "20A_A20") (pintype "bidirectional"))
      (node (ref "R16") (pin "2") (pinfunction "2_2") (pintype "passive"))
    )
    (net (code "60") (name "/{slash}HALT") (class "Default")
      (node (ref "C1") (pin "1") (pinfunction "1_1") (pintype "passive"))
      (node (ref "IC1") (pin "17") (pinfunction "HALT_17") (pintype "output"))
      (node (ref "IC3") (pin "18") (pinfunction "HALT_18") (pintype "output"))
      (node (ref "K1") (pin "A13") (pinfunction "13A_A13") (pintype "bidirectional"))
      (node (ref "R1") (pin "1") (pinfunction "1_1") (pintype "passive"))
    )
    (net (code "61") (name "/{slash}IORQ") (class "Default")
      (node (ref "IC1") (pin "7") (pinfunction "IORQ_7") (pintype "output"))
      (node (ref "IC3") (pin "20") (pinfunction "IORQ_20") (pintype "output"))
      (node (ref "K1") (pin "A15") (pinfunction "15A_A15") (pintype "bidirectional"))
    )
    (net (code "62") (name "/{slash}M1") (class "Default")
      (node (ref "IC1") (pin "10") (pinfunction "M1_10") (pintype "output"))
      (node (ref "IC3") (pin "27") (pinfunction "M1_27") (pintype "output"))
      (node (ref "K1") (pin "A22") (pinfunction "22A_A22") (pintype "bidirectional"))
    )
    (net (code "63") (name "/{slash}MREQ") (class "Default")
      (node (ref "IC1") (pin "9") (pinfunction "MREQ_9") (pintype "output"))
      (node (ref "IC3") (pin "19") (pinfunction "MREQ_19") (pintype "output"))
      (node (ref "K1") (pin "A14") (pinfunction "14A_A14") (pintype "bidirectional"))
    )
    (net (code "64") (name "/{slash}NMI") (class "Default")
      (node (ref "IC1") (pin "15") (pinfunction "NMI_15") (pintype "input"))
      (node (ref "IC3") (pin "17") (pinfunction "NMI_17") (pintype "input"))
      (node (ref "K1") (pin "A12") (pinfunction "12A_A12") (pintype "bidirectional"))
      (node (ref "T1") (pin "E") (pinfunction "E_E") (pintype "passive"))
    )
    (net (code "65") (name "/{slash}RAMCS") (class "Default")
      (node (ref "IC4") (pin "20") (pinfunction "CE_20") (pintype "input"))
      (node (ref "IC4") (pin "22") (pinfunction "OE_22") (pintype "input"))
      (node (ref "IC4A") (pin "8") (pinfunction "CS_8") (pintype "output"))
      (node (ref "IC4B") (pin "8") (pinfunction "CS_8") (pintype "output"))
      (node (ref "K1") (pin "A2") (pinfunction "2A_A2") (pintype "bidirectional"))
      (node (ref "R2") (pin "2") (pinfunction "2_2") (pintype "passive"))
    )
    (net (code "66") (name "/{slash}RD") (class "Default")
      (node (ref "IC1") (pin "6") (pinfunction "RD_6") (pintype "output"))
      (node (ref "IC3") (pin "21") (pinfunction "RD_21") (pintype "output"))
      (node (ref "K1") (pin "A16") (pinfunction "16A_A16") (pintype "bidirectional"))
    )
    (net (code "67") (name "/{slash}RESET") (class "Default")
      (node (ref "C5") (pin "+") (pinfunction "+_+") (pintype "passive"))
      (node (ref "IC3") (pin "26") (pinfunction "RESET_26") (pintype "input"))
      (node (ref "K1") (pin "A21") (pinfunction "21A_A21") (pintype "bidirectional"))
      (node (ref "K5") (pin "6") (pinfunction "6_6") (pintype "bidirectional"))
      (node (ref "R15") (pin "1") (pinfunction "1_1") (pintype "passive"))
      (node (ref "S1") (pin "2") (pinfunction "S_2") (pintype "passive"))
    )
    (net (code "68") (name "/{slash}RFSH") (class "Default")
      (node (ref "IC3") (pin "28") (pinfunction "RFSH_28") (pintype "output"))
      (node (ref "K1") (pin "A23") (pinfunction "23A_A23") (pintype "bidirectional"))
    )
    (net (code "69") (name "/{slash}ROMCS") (class "Default")
      (node (ref "IC2") (pin "20") (pinfunction "CS_20") (pintype "input"))
      (node (ref "IC2") (pin "22") (pinfunction "OE_22") (pintype "input"))
      (node (ref "IC2B") (pin "20") (pinfunction "CS_20") (pintype "output"))
      (node (ref "K1") (pin "B23") (pinfunction "23B_B23") (pintype "bidirectional"))
      (node (ref "R28") (pin "2") (pinfunction "2_2") (pintype "passive"))
    )
    (net (code "70") (name "/{slash}WAIT") (class "Default")
      (node (ref "IC3") (pin "24") (pinfunction "WAIT_24") (pintype "input"))
      (node (ref "K1") (pin "A19") (pinfunction "19A_A19") (pintype "bidirectional"))
      (node (ref "R17") (pin "1") (pinfunction "1_1") (pintype "passive"))
      (node (ref "T1") (pin "C") (pinfunction "C_C") (pintype "passive"))
      (node (ref "T3") (pin "B") (pinfunction "B_B") (pintype "passive"))
    )
    (net (code "71") (name "/{slash}WR") (class "Default")
      (node (ref "IC1") (pin "8") (pinfunction "WR_8") (pintype "output"))
      (node (ref "IC3") (pin "22") (pinfunction "WR_22") (pintype "output"))
      (node (ref "IC4") (pin "27") (pinfunction "WE_27") (pintype "input"))
      (node (ref "IC4A") (pin "10") (pinfunction "WE_10") (pintype "output"))
      (node (ref "IC4B") (pin "10") (pinfunction "WE_10") (pintype "output"))
      (node (ref "K1") (pin "A17") (pinfunction "17A_A17") (pintype "bidirectional"))
    )
    (net (code "72") (name "GND") (class "Default")
      (node (ref "C11") (pin "2") (pinfunction "2_2") (pintype "passive"))
      (node (ref "C2") (pin "2") (pinfunction "2_2") (pintype "passive"))
      (node (ref "C3") (pin "-") (pinfunction "-_-") (pintype "passive"))
      (node (ref "C4") (pin "2") (pinfunction "2_2") (pintype "passive"))
      (node (ref "C5") (pin "-") (pinfunction "-_-") (pintype "passive"))
      (node (ref "C8") (pin "2") (pinfunction "2_2") (pintype "passive"))
      (node (ref "C9") (pin "2") (pinfunction "2_2") (pintype "passive"))
      (node (ref "IC1") (pin "34") (pinfunction "GND_34") (pintype "power_in"))
      (node (ref "IC2") (pin "14") (pinfunction "GND_14") (pintype "power_in"))
      (node (ref "IC2B") (pin "12") (pinfunction "GND_12") (pintype "power_in"))
      (node (ref "IC3") (pin "29") (pinfunction "GND_29") (pintype "power_in"))
      (node (ref "IC4") (pin "14") (pinfunction "GND_14") (pintype "power_in"))
      (node (ref "IC4A") (pin "9") (pinfunction "GND_9") (pintype "power_in"))
      (node (ref "IC4B") (pin "9") (pinfunction "GND_9") (pintype "power_in"))
      (node (ref "JP1") (pin "1") (pinfunction "P$1_1") (pintype "bidirectional"))
      (node (ref "JP2") (pin "1") (pinfunction "P$1_1") (pintype "bidirectional"))
      (node (ref "K1") (pin "B4") (pinfunction "4B_B4") (pintype "bidirectional"))
      (node (ref "K1") (pin "B5") (pinfunction "5B_B5") (pintype "bidirectional"))
      (node (ref "K2") (pin "2") (pinfunction "P$2_2") (pintype "bidirectional"))
      (node (ref "K2") (pin "2'") (pinfunction "P$2'_2'") (pintype "bidirectional"))
      (node (ref "K3") (pin "2") (pinfunction "P$2_2") (pintype "bidirectional"))
      (node (ref "K3") (pin "2'") (pinfunction "P$2'_2'") (pintype "bidirectional"))
      (node (ref "K4") (pin "2") (pinfunction "P$2_2") (pintype "bidirectional"))
      (node (ref "K4") (pin "2'") (pinfunction "P$2'_2'") (pintype "bidirectional"))
      (node (ref "K5") (pin "7") (pinfunction "7_7") (pintype "bidirectional"))
      (node (ref "K5") (pin "8") (pinfunction "8_8") (pintype "bidirectional"))
      (node (ref "R27") (pin "1") (pinfunction "1_1") (pintype "passive"))
      (node (ref "R3") (pin "1") (pinfunction "1_1") (pintype "passive"))
      (node (ref "R30") (pin "2") (pinfunction "2_2") (pintype "passive"))
      (node (ref "R31") (pin "1") (pinfunction "1_1") (pintype "passive"))
      (node (ref "R34") (pin "1") (pinfunction "1_1") (pintype "passive"))
      (node (ref "R4") (pin "1") (pinfunction "1_1") (pintype "passive"))
      (node (ref "REG1") (pin "GND") (pinfunction "GND_GND") (pintype "input"))
      (node (ref "S1") (pin "1") (pinfunction "P_1") (pintype "passive"))
      (node (ref "T2") (pin "E") (pinfunction "E_E") (pintype "passive"))
      (node (ref "X1") (pin "1") (pinfunction "1_1") (pintype "passive"))
    )
    (net (code "73") (name "Net-(C6-Pad2)") (class "Default")
      (node (ref "C6") (pin "2") (pinfunction "2_2") (pintype "passive"))
      (node (ref "X1") (pin "2") (pinfunction "2_2") (pintype "passive"))
    )
    (net (code "74") (name "Net-(C7-Pad2)") (class "Default")
      (node (ref "C7") (pin "2") (pinfunction "2_2") (pintype "passive"))
      (node (ref "R3") (pin "2") (pinfunction "2_2") (pintype "passive"))
      (node (ref "R6") (pin "2") (pinfunction "2_2") (pintype "passive"))
      (node (ref "T2") (pin "B") (pinfunction "B_B") (pintype "passive"))
    )
    (net (code "75") (name "Net-(C10-Pad2)") (class "Default")
      (node (ref "C10") (pin "2") (pinfunction "2_2") (pintype "passive"))
      (node (ref "R33") (pin "1") (pinfunction "1_1") (pintype "passive"))
    )
    (net (code "76") (name "Net-(C12-Pad2)") (class "Default")
      (node (ref "C12") (pin "2") (pinfunction "2_2") (pintype "passive"))
      (node (ref "R29") (pin "1") (pinfunction "1_1") (pintype "passive"))
    )
    (net (code "77") (name "Net-(D9-PadC)") (class "Default")
      (node (ref "D9") (pin "C") (pinfunction "C_C") (pintype "passive"))
      (node (ref "R32") (pin "2") (pinfunction "2_2") (pintype "passive"))
    )
    (net (code "78") (name "Net-(IC1-KBD0)") (class "Default")
      (node (ref "IC1") (pin "33") (pinfunction "KBD0_33") (pintype "output"))
      (node (ref "KB1") (pin "P$1") (pinfunction "1_P$1") (pintype "bidirectional"))
      (node (ref "RP3") (pin "2") (pinfunction "2_2") (pintype "passive"))
    )
    (net (code "79") (name "Net-(IC1-KBD1)") (class "Default")
      (node (ref "IC1") (pin "31") (pinfunction "KBD1_31") (pintype "input"))
      (node (ref "KB1") (pin "P$2") (pinfunction "2_P$2") (pintype "bidirectional"))
      (node (ref "RP3") (pin "3") (pinfunction "3_3") (pintype "passive"))
    )
    (net (code "80") (name "Net-(IC1-KBD2)") (class "Default")
      (node (ref "IC1") (pin "29") (pinfunction "KBD2_29") (pintype "input"))
      (node (ref "KB1") (pin "P$3") (pinfunction "3_P$3") (pintype "bidirectional"))
      (node (ref "RP3") (pin "4") (pinfunction "4_4") (pintype "passive"))
    )
    (net (code "81") (name "Net-(IC1-KBD3)") (class "Default")
      (node (ref "IC1") (pin "27") (pinfunction "KBD3_27") (pintype "input"))
      (node (ref "KB1") (pin "P$4") (pinfunction "4_P$4") (pintype "bidirectional"))
      (node (ref "RP3") (pin "5") (pinfunction "5_5") (pintype "passive"))
    )
    (net (code "82") (name "Net-(IC1-KBD4)") (class "Default")
      (node (ref "IC1") (pin "25") (pinfunction "KBD4_25") (pintype "input"))
      (node (ref "KB1") (pin "P$5") (pinfunction "5_P$5") (pintype "bidirectional"))
      (node (ref "RP3") (pin "6") (pinfunction "6_6") (pintype "passive"))
    )
    (net (code "83") (name "Net-(IC1-OSC)") (class "Default")
      (node (ref "C6") (pin "1") (pinfunction "1_1") (pintype "passive"))
      (node (ref "IC1") (pin "35") (pinfunction "OSC_35") (pintype "output"))
      (node (ref "JP3") (pin "1") (pinfunction "P$1_1") (pintype "bidirectional"))
      (node (ref "R4") (pin "2") (pinfunction "2_2") (pintype "passive"))
    )
    (net (code "84") (name "Net-(IC1-RAMCS)") (class "Default")
      (node (ref "IC1") (pin "12") (pinfunction "RAMCS_12") (pintype "output"))
      (node (ref "R2") (pin "1") (pinfunction "1_1") (pintype "passive"))
    )
    (net (code "85") (name "Net-(IC1-ROMCS)") (class "Default")
      (node (ref "IC1") (pin "13") (pinfunction "ROMCS_13") (pintype "output"))
      (node (ref "R28") (pin "1") (pinfunction "1_1") (pintype "passive"))
    )
    (net (code "86") (name "Net-(IC1-TAPE_IN)") (class "Default")
      (node (ref "IC1") (pin "20") (pinfunction "TAPE_IN_20") (pintype "output"))
      (node (ref "R33") (pin "2") (pinfunction "2_2") (pintype "passive"))
    )
    (net (code "87") (name "Net-(IC2-A14)") (class "Default")
      (node (ref "IC2") (pin "27") (pinfunction "A14_27") (pintype "input"))
      (node (ref "JP1") (pin "2") (pinfunction "P$2_2") (pintype "bidirectional"))
      (node (ref "R80") (pin "1") (pinfunction "1_1") (pintype "passive"))
    )
    (net (code "88") (name "Net-(IC2-A15)") (class "Default")
      (node (ref "IC2") (pin "1") (pinfunction "A15_1") (pintype "input"))
      (node (ref "JP2") (pin "2") (pinfunction "P$2_2") (pintype "bidirectional"))
      (node (ref "R81") (pin "1") (pinfunction "1_1") (pintype "passive"))
    )
    (net (code "89") (name "Net-(JP4-P$1)") (class "Default")
      (node (ref "C1") (pin "2") (pinfunction "2_2") (pintype "passive"))
      (node (ref "JP4") (pin "1") (pinfunction "P$1_1") (pintype "bidirectional"))
      (node (ref "R1") (pin "2") (pinfunction "2_2") (pintype "passive"))
      (node (ref "T1") (pin "B") (pinfunction "B_B") (pintype "passive"))
    )
    (net (code "90") (name "Net-(JP4-P$2)") (class "Default")
      (node (ref "JP4") (pin "2") (pinfunction "P$2_2") (pintype "bidirectional"))
      (node (ref "T3") (pin "C") (pinfunction "C_C") (pintype "passive"))
    )
    (net (code "91") (name "Net-(K2-P$1')") (class "Default")
      (node (ref "C11") (pin "1") (pinfunction "1_1") (pintype "passive"))
      (node (ref "C12") (pin "1") (pinfunction "1_1") (pintype "passive"))
      (node (ref "K2") (pin "1") (pinfunction "P$1_1") (pintype "bidirectional"))
      (node (ref "K2") (pin "1'") (pinfunction "P$1'_1'") (pintype "bidirectional"))
      (node (ref "R27") (pin "2") (pinfunction "2_2") (pintype "passive"))
    )
    (net (code "92") (name "Net-(KB2-1)") (class "Default")
      (node (ref "D1") (pin "A") (pinfunction "A_A") (pintype "passive"))
      (node (ref "KB2") (pin "P$1") (pinfunction "1_P$1") (pintype "bidirectional"))
    )
    (net (code "93") (name "Net-(KB2-2)") (class "Default")
      (node (ref "D2") (pin "A") (pinfunction "A_A") (pintype "passive"))
      (node (ref "KB2") (pin "P$2") (pinfunction "2_P$2") (pintype "bidirectional"))
    )
    (net (code "94") (name "Net-(KB2-3)") (class "Default")
      (node (ref "D3") (pin "A") (pinfunction "A_A") (pintype "passive"))
      (node (ref "KB2") (pin "P$3") (pinfunction "3_P$3") (pintype "bidirectional"))
    )
    (net (code "95") (name "Net-(KB2-4)") (class "Default")
      (node (ref "D4") (pin "A") (pinfunction "A_A") (pintype "passive"))
      (node (ref "KB2") (pin "P$4") (pinfunction "4_P$4") (pintype "bidirectional"))
    )
    (net (code "96") (name "Net-(KB2-5)") (class "Default")
      (node (ref "D5") (pin "A") (pinfunction "A_A") (pintype "passive"))
      (node (ref "KB2") (pin "P$5") (pinfunction "5_P$5") (pintype "bidirectional"))
    )
    (net (code "97") (name "Net-(KB2-6)") (class "Default")
      (node (ref "D6") (pin "A") (pinfunction "A_A") (pintype "passive"))
      (node (ref "KB2") (pin "P$6") (pinfunction "6_P$6") (pintype "bidirectional"))
    )
    (net (code "98") (name "Net-(KB2-7)") (class "Default")
      (node (ref "D7") (pin "A") (pinfunction "A_A") (pintype "passive"))
      (node (ref "KB2") (pin "P$7") (pinfunction "7_P$7") (pintype "bidirectional"))
    )
    (net (code "99") (name "Net-(KB2-8)") (class "Default")
      (node (ref "D8") (pin "A") (pinfunction "A_A") (pintype "passive"))
      (node (ref "KB2") (pin "P$8") (pinfunction "8_P$8") (pintype "bidirectional"))
    )
    (net (code "100") (name "Net-(R31-Pad2)") (class "Default")
      (node (ref "R31") (pin "2") (pinfunction "2_2") (pintype "passive"))
      (node (ref "R32") (pin "1") (pinfunction "1_1") (pintype "passive"))
    )
    (net (code "101") (name "Net-(R35-Pad1)") (class "Default")
      (node (ref "R35") (pin "1") (pinfunction "1_1") (pintype "passive"))
      (node (ref "T3") (pin "E") (pinfunction "E_E") (pintype "passive"))
    )
  )
)
